# HSS.net
KiCad netlist of a schematic drawn in Altium Designer
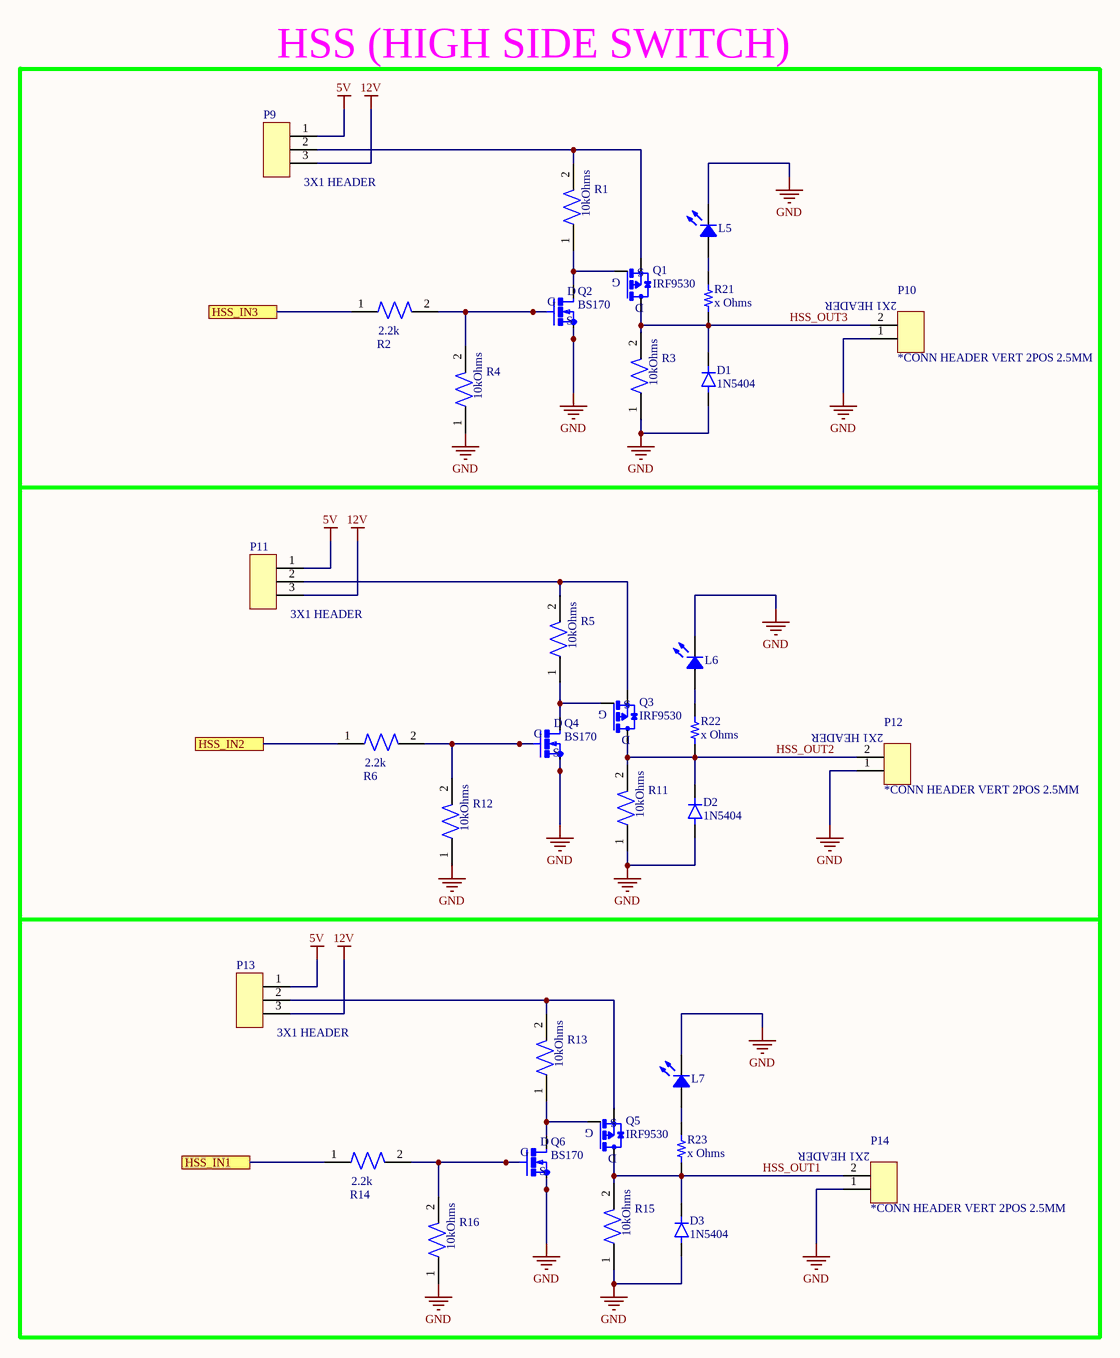
[diagram p0: HSS.SchDoc]

(export (version "E")
  (design (tool "Eeschema 10.0.6"))
  (components
    (comp (ref "D1")
      (value "1N5404")
      (footprint "DIOAD1990W125L900D530")
      (description "Diode Standard 400 V 3A Through Hole DO-201AD")
      (fields (field (name "MF") "ON Semiconductor"))
      (libsource (lib "1N5404") (part "1N5404"))
    )
    (comp (ref "D2")
      (value "1N5404")
      (footprint "DIOAD1990W125L900D530")
      (description "Diode Standard 400 V 3A Through Hole DO-201AD")
      (fields (field (name "MF") "ON Semiconductor"))
      (libsource (lib "1N5404") (part "1N5404"))
    )
    (comp (ref "D3")
      (value "1N5404")
      (footprint "DIOAD1990W125L900D530")
      (description "Diode Standard 400 V 3A Through Hole DO-201AD")
      (fields (field (name "MF") "ON Semiconductor"))
      (libsource (lib "1N5404") (part "1N5404"))
    )
    (comp (ref "L5") (value "LED_SMD") (footprint "LED_SMD") (libsource (lib "Schlib1") (part "LED_SMD")))
    (comp (ref "L6") (value "LED_SMD") (footprint "LED_SMD") (libsource (lib "Schlib1") (part "LED_SMD")))
    (comp (ref "L7") (value "LED_SMD") (footprint "LED_SMD") (libsource (lib "Schlib1") (part "LED_SMD")))
    (comp (ref "P9")
      (value "CONN HEADER VERT 3POS 2.5MM")
      (footprint "2132230-3")
      (description "Conn Shrouded Header HDR 3Power POS 2.5mm Solder ST Top Entry Thru-Hole Bag")
      (fields
        (field (name "MANUFACTURER") "TE Connectivity")
        (field (name "MANUFACTURER PART NUMBER") "2132230-3")
      )
      (libsource (lib "Schlib1") (part "2132230-3"))
    )
    (comp (ref "P10")
      (value "*CONN HEADER VERT 2POS 2.5MM")
      (footprint "51025-02-0100-01")
      (description "Conn Shrouded Header (4 Sides) HDR 2 POS 2.5mm Solder ST Top Entry Thru-Hole Box")
      (fields
        (field (name "MANUFACTURER") "JST")
        (field (name "MANUFACTURER PART NUMBER") "B2B-XH-A(LF)(SN)")
      )
      (libsource (lib "Schlib1") (part "B2B-XH-AM(LF)(SN)"))
    )
    (comp (ref "P11")
      (value "CONN HEADER VERT 3POS 2.5MM")
      (footprint "2132230-3")
      (description "Conn Shrouded Header HDR 3Power POS 2.5mm Solder ST Top Entry Thru-Hole Bag")
      (fields
        (field (name "MANUFACTURER") "TE Connectivity")
        (field (name "MANUFACTURER PART NUMBER") "2132230-3")
      )
      (libsource (lib "Schlib1") (part "2132230-3"))
    )
    (comp (ref "P12")
      (value "*CONN HEADER VERT 2POS 2.5MM")
      (footprint "51025-02-0100-01")
      (description "Conn Shrouded Header (4 Sides) HDR 2 POS 2.5mm Solder ST Top Entry Thru-Hole Box")
      (fields
        (field (name "MANUFACTURER") "JST")
        (field (name "MANUFACTURER PART NUMBER") "B2B-XH-A(LF)(SN)")
      )
      (libsource (lib "Schlib1") (part "B2B-XH-AM(LF)(SN)"))
    )
    (comp (ref "P13")
      (value "CONN HEADER VERT 3POS 2.5MM")
      (footprint "2132230-3")
      (description "Conn Shrouded Header HDR 3Power POS 2.5mm Solder ST Top Entry Thru-Hole Bag")
      (fields
        (field (name "MANUFACTURER") "TE Connectivity")
        (field (name "MANUFACTURER PART NUMBER") "2132230-3")
      )
      (libsource (lib "Schlib1") (part "2132230-3"))
    )
    (comp (ref "P14")
      (value "*CONN HEADER VERT 2POS 2.5MM")
      (footprint "51025-02-0100-01")
      (description "Conn Shrouded Header (4 Sides) HDR 2 POS 2.5mm Solder ST Top Entry Thru-Hole Box")
      (fields
        (field (name "MANUFACTURER") "JST")
        (field (name "MANUFACTURER PART NUMBER") "B2B-XH-A(LF)(SN)")
      )
      (libsource (lib "Schlib1") (part "B2B-XH-AM(LF)(SN)"))
    )
    (comp (ref "Q1")
      (value "IRF9530")
      (footprint "DPAK508P1524X483-3N")
      (description "P-Channel 100V 14A _Tc_ 79W _Tc_ Through Hole TO-220AB")
      (fields (field (name "MF") "Vishay"))
      (libsource (lib "IRF9530") (part "IRF9530"))
    )
    (comp (ref "Q2")
      (value "BS170")
      (footprint "SOT91P240X120-3N")
      (description "N-Channel 60 V 500mA (Ta) 830mW (Ta) Through Hole TO-92-3")
      (fields (field (name "MF") "ON Semiconductor"))
      (libsource (lib "BS170") (part "BS170"))
    )
    (comp (ref "Q3")
      (value "IRF9530")
      (footprint "DPAK508P1524X483-3N")
      (description "P-Channel 100V 14A _Tc_ 79W _Tc_ Through Hole TO-220AB")
      (fields (field (name "MF") "Vishay"))
      (libsource (lib "IRF9530") (part "IRF9530"))
    )
    (comp (ref "Q4")
      (value "BS170")
      (footprint "SOT91P240X120-3N")
      (description "N-Channel 60 V 500mA (Ta) 830mW (Ta) Through Hole TO-92-3")
      (fields (field (name "MF") "ON Semiconductor"))
      (libsource (lib "BS170") (part "BS170"))
    )
    (comp (ref "Q5")
      (value "IRF9530")
      (footprint "DPAK508P1524X483-3N")
      (description "P-Channel 100V 14A _Tc_ 79W _Tc_ Through Hole TO-220AB")
      (fields (field (name "MF") "Vishay"))
      (libsource (lib "IRF9530") (part "IRF9530"))
    )
    (comp (ref "Q6")
      (value "BS170")
      (footprint "SOT91P240X120-3N")
      (description "N-Channel 60 V 500mA (Ta) 830mW (Ta) Through Hole TO-92-3")
      (fields (field (name "MF") "ON Semiconductor"))
      (libsource (lib "BS170") (part "BS170"))
    )
    (comp (ref "R1")
      (value "RES 10K OHM 1% 1/8W 0805")
      (footprint "RES 1206_3216 RF")
      (description "Res Thick Film 2.0 x 1.2 mm 10K Ohm 1% 0.125W(1/8W) 100ppm/ C Molded SMD Paper T/R")
      (fields
        (field (name "MANUFACTURER") "Yageo")
        (field (name "MANUFACTURER PART NUMBER") "RC0805FR-1310KL")
      )
      (libsource (lib "Schlib1") (part "RC0805FR-1310KL"))
    )
    (comp (ref "R2")
      (value "RES 10K OHM 1% 1/8W 0805")
      (footprint "RES 0805_2012")
      (fields
        (field (name "MANUFACTURER") "Vishay")
        (field (name "MANUFACTURER PART NUMBER") "CRCW06032K20FKEAHP")
        (field (name "TOLERANCE") "1%")
      )
      (libsource (lib "Schlib1") (part "2.2k dip"))
    )
    (comp (ref "R3")
      (value "RES 10K OHM 1% 1/8W 0805")
      (footprint "RES 1206_3216 RF")
      (description "Res Thick Film 2.0 x 1.2 mm 10K Ohm 1% 0.125W(1/8W) 100ppm/ C Molded SMD Paper T/R")
      (fields
        (field (name "MANUFACTURER") "Yageo")
        (field (name "MANUFACTURER PART NUMBER") "RC0805FR-1310KL")
      )
      (libsource (lib "Schlib1") (part "RC0805FR-1310KL"))
    )
    (comp (ref "R4")
      (value "RES 10K OHM 1% 1/8W 0805")
      (footprint "RES 1206_3216 RF")
      (description "Res Thick Film 2.0 x 1.2 mm 10K Ohm 1% 0.125W(1/8W) 100ppm/ C Molded SMD Paper T/R")
      (fields
        (field (name "MANUFACTURER") "Yageo")
        (field (name "MANUFACTURER PART NUMBER") "RC0805FR-1310KL")
      )
      (libsource (lib "Schlib1") (part "RC0805FR-1310KL"))
    )
    (comp (ref "R5")
      (value "RES 10K OHM 1% 1/8W 0805")
      (footprint "RES 1206_3216 RF")
      (description "Res Thick Film 2.0 x 1.2 mm 10K Ohm 1% 0.125W(1/8W) 100ppm/ C Molded SMD Paper T/R")
      (fields
        (field (name "MANUFACTURER") "Yageo")
        (field (name "MANUFACTURER PART NUMBER") "RC0805FR-1310KL")
      )
      (libsource (lib "Schlib1") (part "RC0805FR-1310KL"))
    )
    (comp (ref "R6")
      (value "RES 10K OHM 1% 1/8W 0805")
      (footprint "RES 0805_2012")
      (fields
        (field (name "MANUFACTURER") "Vishay")
        (field (name "MANUFACTURER PART NUMBER") "CRCW06032K20FKEAHP")
        (field (name "TOLERANCE") "1%")
      )
      (libsource (lib "Schlib1") (part "2.2k dip"))
    )
    (comp (ref "R11")
      (value "RES 10K OHM 1% 1/8W 0805")
      (footprint "RES 1206_3216 RF")
      (description "Res Thick Film 2.0 x 1.2 mm 10K Ohm 1% 0.125W(1/8W) 100ppm/ C Molded SMD Paper T/R")
      (fields
        (field (name "MANUFACTURER") "Yageo")
        (field (name "MANUFACTURER PART NUMBER") "RC0805FR-1310KL")
      )
      (libsource (lib "Schlib1") (part "RC0805FR-1310KL"))
    )
    (comp (ref "R12")
      (value "RES 10K OHM 1% 1/8W 0805")
      (footprint "RES 1206_3216 RF")
      (description "Res Thick Film 2.0 x 1.2 mm 10K Ohm 1% 0.125W(1/8W) 100ppm/ C Molded SMD Paper T/R")
      (fields
        (field (name "MANUFACTURER") "Yageo")
        (field (name "MANUFACTURER PART NUMBER") "RC0805FR-1310KL")
      )
      (libsource (lib "Schlib1") (part "RC0805FR-1310KL"))
    )
    (comp (ref "R13")
      (value "RES 10K OHM 1% 1/8W 0805")
      (footprint "RES 1206_3216 RF")
      (description "Res Thick Film 2.0 x 1.2 mm 10K Ohm 1% 0.125W(1/8W) 100ppm/ C Molded SMD Paper T/R")
      (fields
        (field (name "MANUFACTURER") "Yageo")
        (field (name "MANUFACTURER PART NUMBER") "RC0805FR-1310KL")
      )
      (libsource (lib "Schlib1") (part "RC0805FR-1310KL"))
    )
    (comp (ref "R14")
      (value "RES 10K OHM 1% 1/8W 0805")
      (footprint "RES 0805_2012")
      (fields
        (field (name "MANUFACTURER") "Vishay")
        (field (name "MANUFACTURER PART NUMBER") "CRCW06032K20FKEAHP")
        (field (name "TOLERANCE") "1%")
      )
      (libsource (lib "Schlib1") (part "2.2k dip"))
    )
    (comp (ref "R15")
      (value "RES 10K OHM 1% 1/8W 0805")
      (footprint "RES 1206_3216 RF")
      (description "Res Thick Film 2.0 x 1.2 mm 10K Ohm 1% 0.125W(1/8W) 100ppm/ C Molded SMD Paper T/R")
      (fields
        (field (name "MANUFACTURER") "Yageo")
        (field (name "MANUFACTURER PART NUMBER") "RC0805FR-1310KL")
      )
      (libsource (lib "Schlib1") (part "RC0805FR-1310KL"))
    )
    (comp (ref "R16")
      (value "RES 10K OHM 1% 1/8W 0805")
      (footprint "RES 1206_3216 RF")
      (description "Res Thick Film 2.0 x 1.2 mm 10K Ohm 1% 0.125W(1/8W) 100ppm/ C Molded SMD Paper T/R")
      (fields
        (field (name "MANUFACTURER") "Yageo")
        (field (name "MANUFACTURER PART NUMBER") "RC0805FR-1310KL")
      )
      (libsource (lib "Schlib1") (part "RC0805FR-1310KL"))
    )
    (comp (ref "R21")
      (value "x Ohms")
      (footprint "RES 1206_3216 RF")
      (description "RES SMD 49.9 OHM 0.1% 1/4W 1206")
      (fields (field (name "PART NUMBER") "RT1206BRD0749R9L") (field (name "MANUFACTURER") "Yageo"))
      (libsource (lib "Celestial Altium Library - altium_library") (part "Resistor"))
    )
    (comp (ref "R22")
      (value "x Ohms")
      (footprint "RES 1206_3216 RF")
      (description "RES SMD 49.9 OHM 0.1% 1/4W 1206")
      (fields (field (name "PART NUMBER") "RT1206BRD0749R9L") (field (name "MANUFACTURER") "Yageo"))
      (libsource (lib "Celestial Altium Library - altium_library") (part "Resistor"))
    )
    (comp (ref "R23")
      (value "x Ohms")
      (footprint "RES 1206_3216 RF")
      (description "RES SMD 49.9 OHM 0.1% 1/4W 1206")
      (fields (field (name "PART NUMBER") "RT1206BRD0749R9L") (field (name "MANUFACTURER") "Yageo"))
      (libsource (lib "Celestial Altium Library - altium_library") (part "Resistor"))
    )
  )
  (nets
    (net (code "1") (name "/HSS_IN1") (class "Default") (node (ref "R14") (pin "1") (pintype "passive")))
    (net (code "2") (name "/HSS_IN2") (class "Default") (node (ref "R6") (pin "1") (pintype "passive")))
    (net (code "3") (name "/HSS_IN3") (class "Default") (node (ref "R2") (pin "1") (pintype "passive")))
    (net (code "4") (name "/HSS_OUT1") (class "Default")
      (node (ref "D3") (pin "C") (pinfunction "K_C") (pintype "passive"))
      (node (ref "P14") (pin "2") (pintype "passive"))
      (node (ref "Q5") (pin "2") (pinfunction "D_2") (pintype "passive"))
      (node (ref "R15") (pin "2") (pintype "passive"))
      (node (ref "R23") (pin "2") (pinfunction "2_2") (pintype "passive"))
    )
    (net (code "5") (name "/HSS_OUT2") (class "Default")
      (node (ref "D2") (pin "C") (pinfunction "K_C") (pintype "passive"))
      (node (ref "P12") (pin "2") (pintype "passive"))
      (node (ref "Q3") (pin "2") (pinfunction "D_2") (pintype "passive"))
      (node (ref "R11") (pin "2") (pintype "passive"))
      (node (ref "R22") (pin "2") (pinfunction "2_2") (pintype "passive"))
    )
    (net (code "6") (name "/HSS_OUT3") (class "Default")
      (node (ref "D1") (pin "C") (pinfunction "K_C") (pintype "passive"))
      (node (ref "P10") (pin "2") (pintype "passive"))
      (node (ref "Q1") (pin "2") (pinfunction "D_2") (pintype "passive"))
      (node (ref "R21") (pin "2") (pinfunction "2_2") (pintype "passive"))
      (node (ref "R3") (pin "2") (pintype "passive"))
    )
    (net (code "7") (name "5V") (class "Default")
      (node (ref "P11") (pin "1") (pintype "passive"))
      (node (ref "P13") (pin "1") (pintype "passive"))
      (node (ref "P9") (pin "1") (pintype "passive"))
    )
    (net (code "8") (name "12V") (class "Default")
      (node (ref "P11") (pin "3") (pintype "passive"))
      (node (ref "P13") (pin "3") (pintype "passive"))
      (node (ref "P9") (pin "3") (pintype "passive"))
    )
    (net (code "9") (name "GND") (class "Default")
      (node (ref "D1") (pin "A") (pinfunction "A_A") (pintype "passive"))
      (node (ref "D2") (pin "A") (pinfunction "A_A") (pintype "passive"))
      (node (ref "D3") (pin "A") (pinfunction "A_A") (pintype "passive"))
      (node (ref "L5") (pin "2") (pinfunction "2_2") (pintype "passive"))
      (node (ref "L6") (pin "2") (pinfunction "2_2") (pintype "passive"))
      (node (ref "L7") (pin "2") (pinfunction "2_2") (pintype "passive"))
      (node (ref "P10") (pin "1") (pintype "passive"))
      (node (ref "P12") (pin "1") (pintype "passive"))
      (node (ref "P14") (pin "1") (pintype "passive"))
      (node (ref "Q2") (pin "S") (pinfunction "S_S") (pintype "passive"))
      (node (ref "Q4") (pin "S") (pinfunction "S_S") (pintype "passive"))
      (node (ref "Q6") (pin "S") (pinfunction "S_S") (pintype "passive"))
      (node (ref "R11") (pin "1") (pintype "passive"))
      (node (ref "R12") (pin "1") (pintype "passive"))
      (node (ref "R15") (pin "1") (pintype "passive"))
      (node (ref "R16") (pin "1") (pintype "passive"))
      (node (ref "R3") (pin "1") (pintype "passive"))
      (node (ref "R4") (pin "1") (pintype "passive"))
    )
    (net (code "10") (name "Net-(L5-Pad1)") (class "Default")
      (node (ref "L5") (pin "1") (pinfunction "1_1") (pintype "passive"))
      (node (ref "R21") (pin "1") (pinfunction "1_1") (pintype "passive"))
    )
    (net (code "11") (name "Net-(L6-Pad1)") (class "Default")
      (node (ref "L6") (pin "1") (pinfunction "1_1") (pintype "passive"))
      (node (ref "R22") (pin "1") (pinfunction "1_1") (pintype "passive"))
    )
    (net (code "12") (name "Net-(L7-Pad1)") (class "Default")
      (node (ref "L7") (pin "1") (pinfunction "1_1") (pintype "passive"))
      (node (ref "R23") (pin "1") (pinfunction "1_1") (pintype "passive"))
    )
    (net (code "13") (name "Net-(Q1-G)") (class "Default")
      (node (ref "Q1") (pin "1") (pinfunction "G_1") (pintype "passive"))
      (node (ref "Q2") (pin "D") (pinfunction "D_D") (pintype "passive"))
      (node (ref "R1") (pin "1") (pintype "passive"))
    )
    (net (code "14") (name "Net-(Q1-S)") (class "Default")
      (node (ref "P9") (pin "2") (pintype "passive"))
      (node (ref "Q1") (pin "3") (pinfunction "S_3") (pintype "passive"))
      (node (ref "R1") (pin "2") (pintype "passive"))
    )
    (net (code "15") (name "Net-(Q2-PadG)") (class "Default")
      (node (ref "Q2") (pin "G") (pinfunction "G_G") (pintype "passive"))
      (node (ref "R2") (pin "2") (pintype "passive"))
      (node (ref "R4") (pin "2") (pintype "passive"))
    )
    (net (code "16") (name "Net-(Q3-G)") (class "Default")
      (node (ref "Q3") (pin "1") (pinfunction "G_1") (pintype "passive"))
      (node (ref "Q4") (pin "D") (pinfunction "D_D") (pintype "passive"))
      (node (ref "R5") (pin "1") (pintype "passive"))
    )
    (net (code "17") (name "Net-(Q3-S)") (class "Default")
      (node (ref "P11") (pin "2") (pintype "passive"))
      (node (ref "Q3") (pin "3") (pinfunction "S_3") (pintype "passive"))
      (node (ref "R5") (pin "2") (pintype "passive"))
    )
    (net (code "18") (name "Net-(Q4-PadG)") (class "Default")
      (node (ref "Q4") (pin "G") (pinfunction "G_G") (pintype "passive"))
      (node (ref "R12") (pin "2") (pintype "passive"))
      (node (ref "R6") (pin "2") (pintype "passive"))
    )
    (net (code "19") (name "Net-(Q5-G)") (class "Default")
      (node (ref "Q5") (pin "1") (pinfunction "G_1") (pintype "passive"))
      (node (ref "Q6") (pin "D") (pinfunction "D_D") (pintype "passive"))
      (node (ref "R13") (pin "1") (pintype "passive"))
    )
    (net (code "20") (name "Net-(Q5-S)") (class "Default")
      (node (ref "P13") (pin "2") (pintype "passive"))
      (node (ref "Q5") (pin "3") (pinfunction "S_3") (pintype "passive"))
      (node (ref "R13") (pin "2") (pintype "passive"))
    )
    (net (code "21") (name "Net-(Q6-PadG)") (class "Default")
      (node (ref "Q6") (pin "G") (pinfunction "G_G") (pintype "passive"))
      (node (ref "R14") (pin "2") (pintype "passive"))
      (node (ref "R16") (pin "2") (pintype "passive"))
    )
  )
)
